# Top.net
KiCad netlist of a schematic drawn in Altium Designer
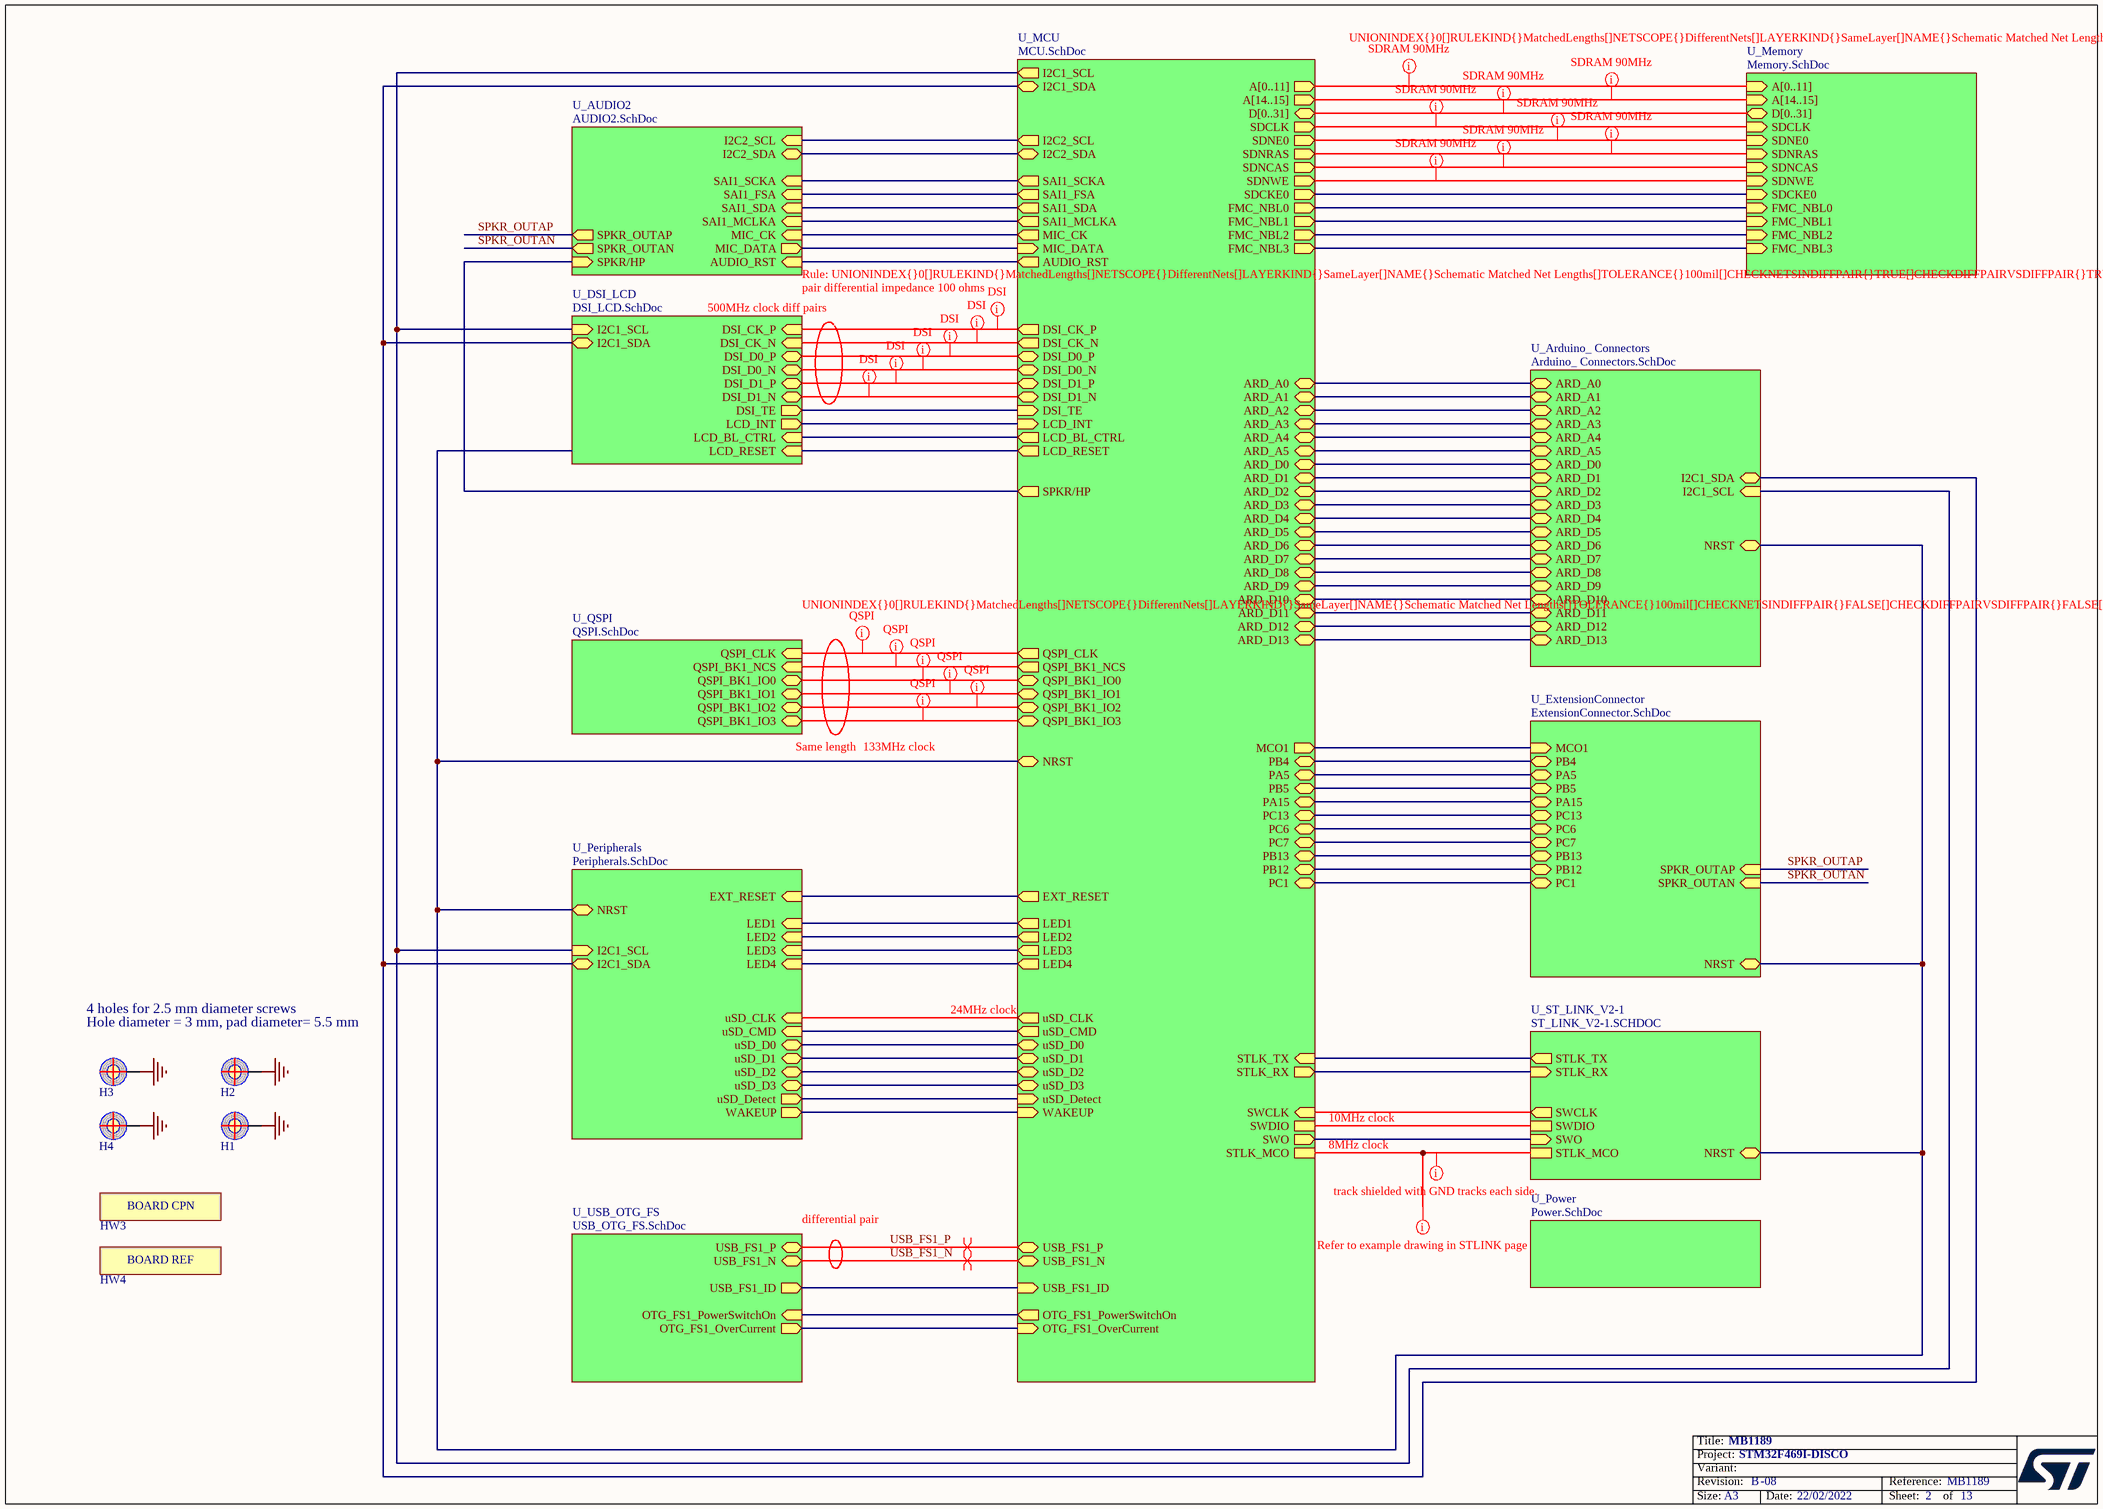
[diagram p0: Top.SchDoc]

(export (version "E")
  (design (tool "Eeschema 10.0.6"))
  (components
    (comp (ref "H1")
      (value "POSITION HOLE")
      (footprint "HOLE_C5R5D3")
      (libsource (lib "mb1045") (part "POSITION HOLE"))
    )
    (comp (ref "H2")
      (value "POSITION HOLE")
      (footprint "HOLE_C5R5D3")
      (libsource (lib "mb1045") (part "POSITION HOLE"))
    )
    (comp (ref "H3")
      (value "POSITION HOLE")
      (footprint "HOLE_C5R5D3")
      (libsource (lib "mb1045") (part "POSITION HOLE"))
    )
    (comp (ref "H4")
      (value "POSITION HOLE")
      (footprint "HOLE_C5R5D3")
      (libsource (lib "mb1045") (part "POSITION HOLE"))
    )
    (comp (ref "HW3")
      (value "STICKER_BOARD_CPN")
      (footprint "STICKER_BOARD-CPN_13X3")
      (libsource (lib "MB1189") (part "STICKER_BOARD_CPN"))
    )
    (comp (ref "HW4")
      (value "STICKER_BOARD_REF")
      (footprint "STICKER_25X9")
      (libsource (lib "MB1189") (part "STICKER_BOARD_REF"))
    )
  )
  (nets
    (net (code "100") (name "GND") (class "Default")
      (node (ref "H1") (pin "1") (pinfunction "1_1") (pintype "passive"))
      (node (ref "H2") (pin "1") (pinfunction "1_1") (pintype "passive"))
      (node (ref "H3") (pin "1") (pinfunction "1_1") (pintype "passive"))
      (node (ref "H4") (pin "1") (pinfunction "1_1") (pintype "passive"))
    )
  )
)
